# Sheet1.net
KiCad netlist of a schematic drawn in Altium Designer
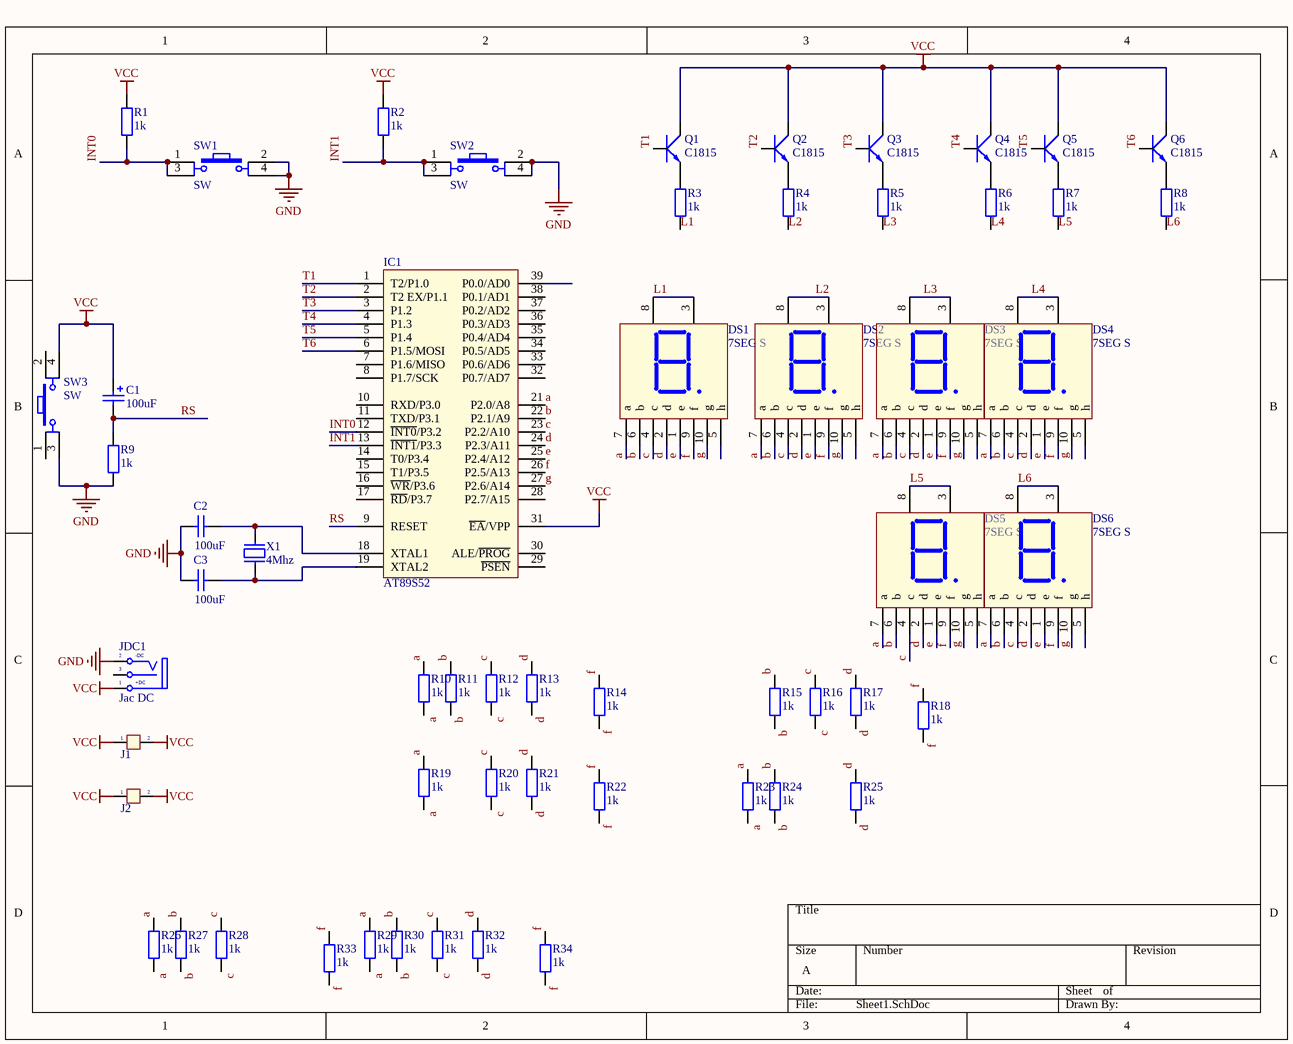
[diagram p0: Sheet1.SchDoc]

(export (version "E")
  (design (tool "Eeschema 10.0.6"))
  (components
    (comp (ref "C1")
      (value "100uF")
      (footprint "RADIAL C")
      (description "Polarized Capacitor")
      (fields (field (name "Comment") "Cap Pol") (field (name "PUBLISHER") "Altium Limited"))
      (libsource (lib "hphonglib") (part "Cap Pol"))
    )
    (comp (ref "C2")
      (value "100uF")
      (footprint "Cap Non-Pol 3mm")
      (description "Non-polarized Capacitor")
      (fields (field (name "Comment") "Cap Non-pol") (field (name "PUBLISHER") "Altium Limited"))
      (libsource (lib "hphonglib") (part "Cap Non-pol"))
    )
    (comp (ref "C3")
      (value "100uF")
      (footprint "Cap Non-Pol 3mm")
      (description "Non-polarized Capacitor")
      (fields (field (name "Comment") "Cap Non-pol") (field (name "PUBLISHER") "Altium Limited"))
      (libsource (lib "hphonglib") (part "Cap Non-pol"))
    )
    (comp (ref "DS1")
      (value "7SEG S")
      (footprint "7SEGS")
      (description "Single 7 Seg Dipslay")
      (libsource (lib "syhaunguyen") (part "LED7S"))
    )
    (comp (ref "DS2")
      (value "7SEG S")
      (footprint "7SEGS")
      (description "Single 7 Seg Dipslay")
      (libsource (lib "syhaunguyen") (part "LED7S"))
    )
    (comp (ref "DS3")
      (value "7SEG S")
      (footprint "7SEGS")
      (description "Single 7 Seg Dipslay")
      (libsource (lib "syhaunguyen") (part "LED7S"))
    )
    (comp (ref "DS4")
      (value "7SEG S")
      (footprint "7SEGS")
      (description "Single 7 Seg Dipslay")
      (libsource (lib "syhaunguyen") (part "LED7S"))
    )
    (comp (ref "DS5")
      (value "7SEG S")
      (footprint "7SEGS")
      (description "Single 7 Seg Dipslay")
      (libsource (lib "syhaunguyen") (part "LED7S"))
    )
    (comp (ref "DS6")
      (value "7SEG S")
      (footprint "7SEGS")
      (description "Single 7 Seg Dipslay")
      (libsource (lib "syhaunguyen") (part "LED7S"))
    )
    (comp (ref "IC1")
      (value "AT89S52")
      (footprint "DIP40/W0.6")
      (description "AT89S52, 8k Byte Flash Memory , 40 Pin")
      (libsource (lib "syhaunguyen") (part "AT89S52"))
    )
    (comp (ref "J1") (value "Jumper 2") (footprint "JP2") (libsource (lib "syhaunguyen") (part "JP 2")))
    (comp (ref "J2") (value "Jumper 2") (footprint "JP2") (libsource (lib "syhaunguyen") (part "JP 2")))
    (comp (ref "JDC1")
      (value "Jac DC")
      (footprint "DC-IN")
      (description "Jac DC input")
      (libsource (lib "syhaunguyen") (part "DCIN"))
    )
    (comp (ref "Q1")
      (value "C1815")
      (footprint "QTO-92")
      (description "NPN 600mW, ECB")
      (libsource (lib "hphonglib") (part "C1815_1"))
    )
    (comp (ref "Q2")
      (value "C1815")
      (footprint "QTO-92")
      (description "NPN 600mW, ECB")
      (libsource (lib "hphonglib") (part "C1815_1"))
    )
    (comp (ref "Q3")
      (value "C1815")
      (footprint "QTO-92")
      (description "NPN 600mW, ECB")
      (libsource (lib "hphonglib") (part "C1815_1"))
    )
    (comp (ref "Q4")
      (value "C1815")
      (footprint "QTO-92")
      (description "NPN 600mW, ECB")
      (libsource (lib "hphonglib") (part "C1815_1"))
    )
    (comp (ref "Q5")
      (value "C1815")
      (footprint "QTO-92")
      (description "NPN 600mW, ECB")
      (libsource (lib "hphonglib") (part "C1815_1"))
    )
    (comp (ref "Q6")
      (value "C1815")
      (footprint "QTO-92")
      (description "NPN 600mW, ECB")
      (libsource (lib "hphonglib") (part "C1815_1"))
    )
    (comp (ref "R1")
      (value "1k")
      (footprint "R1/4W")
      (description "Resistor 1/4W")
      (libsource (lib "syhaunguyen") (part "R1/4W"))
    )
    (comp (ref "R2")
      (value "1k")
      (footprint "R1/4W")
      (description "Resistor 1/4W")
      (libsource (lib "syhaunguyen") (part "R1/4W"))
    )
    (comp (ref "R3")
      (value "1k")
      (footprint "R1/4W")
      (description "Resistor 1/4W")
      (libsource (lib "syhaunguyen") (part "R1/4W"))
    )
    (comp (ref "R4")
      (value "1k")
      (footprint "R1/4W")
      (description "Resistor 1/4W")
      (libsource (lib "syhaunguyen") (part "R1/4W"))
    )
    (comp (ref "R5")
      (value "1k")
      (footprint "R1/4W")
      (description "Resistor 1/4W")
      (libsource (lib "syhaunguyen") (part "R1/4W"))
    )
    (comp (ref "R6")
      (value "1k")
      (footprint "R1/4W")
      (description "Resistor 1/4W")
      (libsource (lib "syhaunguyen") (part "R1/4W"))
    )
    (comp (ref "R7")
      (value "1k")
      (footprint "R1/4W")
      (description "Resistor 1/4W")
      (libsource (lib "syhaunguyen") (part "R1/4W"))
    )
    (comp (ref "R8")
      (value "1k")
      (footprint "R1/4W")
      (description "Resistor 1/4W")
      (libsource (lib "syhaunguyen") (part "R1/4W"))
    )
    (comp (ref "R9")
      (value "1k")
      (footprint "R1/4W")
      (description "Resistor 1/4W")
      (libsource (lib "syhaunguyen") (part "R1/4W"))
    )
    (comp (ref "R10")
      (value "1k")
      (footprint "R1/4W")
      (description "Resistor 1/4W")
      (libsource (lib "syhaunguyen") (part "R1/4W"))
    )
    (comp (ref "R11")
      (value "1k")
      (footprint "R1/4W")
      (description "Resistor 1/4W")
      (libsource (lib "syhaunguyen") (part "R1/4W"))
    )
    (comp (ref "R12")
      (value "1k")
      (footprint "R1/4W")
      (description "Resistor 1/4W")
      (libsource (lib "syhaunguyen") (part "R1/4W"))
    )
    (comp (ref "R13")
      (value "1k")
      (footprint "R1/4W")
      (description "Resistor 1/4W")
      (libsource (lib "syhaunguyen") (part "R1/4W"))
    )
    (comp (ref "R14")
      (value "1k")
      (footprint "R1/4W")
      (description "Resistor 1/4W")
      (libsource (lib "syhaunguyen") (part "R1/4W"))
    )
    (comp (ref "R15")
      (value "1k")
      (footprint "R1/4W")
      (description "Resistor 1/4W")
      (libsource (lib "syhaunguyen") (part "R1/4W"))
    )
    (comp (ref "R16")
      (value "1k")
      (footprint "R1/4W")
      (description "Resistor 1/4W")
      (libsource (lib "syhaunguyen") (part "R1/4W"))
    )
    (comp (ref "R17")
      (value "1k")
      (footprint "R1/4W")
      (description "Resistor 1/4W")
      (libsource (lib "syhaunguyen") (part "R1/4W"))
    )
    (comp (ref "R18")
      (value "1k")
      (footprint "R1/4W")
      (description "Resistor 1/4W")
      (libsource (lib "syhaunguyen") (part "R1/4W"))
    )
    (comp (ref "R19")
      (value "1k")
      (footprint "R1/4W")
      (description "Resistor 1/4W")
      (libsource (lib "syhaunguyen") (part "R1/4W"))
    )
    (comp (ref "R20")
      (value "1k")
      (footprint "R1/4W")
      (description "Resistor 1/4W")
      (libsource (lib "syhaunguyen") (part "R1/4W"))
    )
    (comp (ref "R21")
      (value "1k")
      (footprint "R1/4W")
      (description "Resistor 1/4W")
      (libsource (lib "syhaunguyen") (part "R1/4W"))
    )
    (comp (ref "R22")
      (value "1k")
      (footprint "R1/4W")
      (description "Resistor 1/4W")
      (libsource (lib "syhaunguyen") (part "R1/4W"))
    )
    (comp (ref "R23")
      (value "1k")
      (footprint "R1/4W")
      (description "Resistor 1/4W")
      (libsource (lib "syhaunguyen") (part "R1/4W"))
    )
    (comp (ref "R24")
      (value "1k")
      (footprint "R1/4W")
      (description "Resistor 1/4W")
      (libsource (lib "syhaunguyen") (part "R1/4W"))
    )
    (comp (ref "R25")
      (value "1k")
      (footprint "R1/4W")
      (description "Resistor 1/4W")
      (libsource (lib "syhaunguyen") (part "R1/4W"))
    )
    (comp (ref "R26")
      (value "1k")
      (footprint "R1/4W")
      (description "Resistor 1/4W")
      (libsource (lib "syhaunguyen") (part "R1/4W"))
    )
    (comp (ref "R27")
      (value "1k")
      (footprint "R1/4W")
      (description "Resistor 1/4W")
      (libsource (lib "syhaunguyen") (part "R1/4W"))
    )
    (comp (ref "R28")
      (value "1k")
      (footprint "R1/4W")
      (description "Resistor 1/4W")
      (libsource (lib "syhaunguyen") (part "R1/4W"))
    )
    (comp (ref "R29")
      (value "1k")
      (footprint "R1/4W")
      (description "Resistor 1/4W")
      (libsource (lib "syhaunguyen") (part "R1/4W"))
    )
    (comp (ref "R30")
      (value "1k")
      (footprint "R1/4W")
      (description "Resistor 1/4W")
      (libsource (lib "syhaunguyen") (part "R1/4W"))
    )
    (comp (ref "R31")
      (value "1k")
      (footprint "R1/4W")
      (description "Resistor 1/4W")
      (libsource (lib "syhaunguyen") (part "R1/4W"))
    )
    (comp (ref "R32")
      (value "1k")
      (footprint "R1/4W")
      (description "Resistor 1/4W")
      (libsource (lib "syhaunguyen") (part "R1/4W"))
    )
    (comp (ref "R33")
      (value "1k")
      (footprint "R1/4W")
      (description "Resistor 1/4W")
      (libsource (lib "syhaunguyen") (part "R1/4W"))
    )
    (comp (ref "R34")
      (value "1k")
      (footprint "R1/4W")
      (description "Resistor 1/4W")
      (libsource (lib "syhaunguyen") (part "R1/4W"))
    )
    (comp (ref "SW1")
      (value "SW")
      (footprint "SW4")
      (description "Switch button 4 pin")
      (libsource (lib "syhaunguyen") (part "SW4"))
    )
    (comp (ref "SW2")
      (value "SW")
      (footprint "SW4")
      (description "Switch button 4 pin")
      (libsource (lib "syhaunguyen") (part "SW4"))
    )
    (comp (ref "SW3")
      (value "SW")
      (footprint "SW4")
      (description "Switch button 4 pin")
      (libsource (lib "") (part "SW4_1"))
    )
    (comp (ref "X1")
      (value "4Mhz")
      (footprint "XT2")
      (description "Crystal For all Crystal 2pin.")
      (libsource (lib "syhaunguyen") (part "XT2"))
    )
  )
  (nets
    (net (code "1") (name "/INT0") (class "Default")
      (node (ref "IC1") (pin "12") (pinfunction "~{INT0}/P3.2_12") (pintype "passive"))
      (node (ref "R1") (pin "2") (pinfunction "2_2") (pintype "passive"))
      (node (ref "SW1") (pin "1") (pintype "passive"))
      (node (ref "SW1") (pin "3") (pintype "passive"))
    )
    (net (code "2") (name "/INT1") (class "Default")
      (node (ref "IC1") (pin "13") (pinfunction "~{INT1}/P3.3_13") (pintype "passive"))
      (node (ref "R2") (pin "2") (pinfunction "2_2") (pintype "passive"))
      (node (ref "SW2") (pin "1") (pintype "passive"))
      (node (ref "SW2") (pin "3") (pintype "passive"))
    )
    (net (code "3") (name "/L1") (class "Default")
      (node (ref "DS1") (pin "3") (pinfunction "Vcc_3") (pintype "passive"))
      (node (ref "DS1") (pin "8") (pinfunction "Vcc_8") (pintype "passive"))
      (node (ref "R3") (pin "1") (pinfunction "1_1") (pintype "passive"))
    )
    (net (code "4") (name "/L2") (class "Default")
      (node (ref "DS2") (pin "3") (pinfunction "Vcc_3") (pintype "passive"))
      (node (ref "DS2") (pin "8") (pinfunction "Vcc_8") (pintype "passive"))
      (node (ref "R4") (pin "1") (pinfunction "1_1") (pintype "passive"))
    )
    (net (code "5") (name "/L3") (class "Default")
      (node (ref "DS3") (pin "3") (pinfunction "Vcc_3") (pintype "passive"))
      (node (ref "DS3") (pin "8") (pinfunction "Vcc_8") (pintype "passive"))
      (node (ref "R5") (pin "1") (pinfunction "1_1") (pintype "passive"))
    )
    (net (code "6") (name "/L4") (class "Default")
      (node (ref "DS4") (pin "3") (pinfunction "Vcc_3") (pintype "passive"))
      (node (ref "DS4") (pin "8") (pinfunction "Vcc_8") (pintype "passive"))
      (node (ref "R6") (pin "1") (pinfunction "1_1") (pintype "passive"))
    )
    (net (code "7") (name "/L5") (class "Default")
      (node (ref "DS5") (pin "3") (pinfunction "Vcc_3") (pintype "passive"))
      (node (ref "DS5") (pin "8") (pinfunction "Vcc_8") (pintype "passive"))
      (node (ref "R7") (pin "1") (pinfunction "1_1") (pintype "passive"))
    )
    (net (code "8") (name "/L6") (class "Default")
      (node (ref "DS6") (pin "3") (pinfunction "Vcc_3") (pintype "passive"))
      (node (ref "DS6") (pin "8") (pinfunction "Vcc_8") (pintype "passive"))
      (node (ref "R8") (pin "1") (pinfunction "1_1") (pintype "passive"))
    )
    (net (code "9") (name "/RS") (class "Default")
      (node (ref "C1") (pin "2") (pinfunction "2_2") (pintype "passive"))
      (node (ref "IC1") (pin "9") (pinfunction "RESET_9") (pintype "passive"))
      (node (ref "R9") (pin "2") (pinfunction "2_2") (pintype "passive"))
    )
    (net (code "10") (name "/T1") (class "Default")
      (node (ref "IC1") (pin "1") (pinfunction "T2/P1.0_1") (pintype "passive"))
      (node (ref "Q1") (pin "3") (pinfunction "B_3") (pintype "passive"))
    )
    (net (code "11") (name "/T2") (class "Default")
      (node (ref "IC1") (pin "2") (pinfunction "T2_EX/P1.1_2") (pintype "passive"))
      (node (ref "Q2") (pin "3") (pinfunction "B_3") (pintype "passive"))
    )
    (net (code "12") (name "/T3") (class "Default")
      (node (ref "IC1") (pin "3") (pinfunction "P1.2_3") (pintype "passive"))
      (node (ref "Q3") (pin "3") (pinfunction "B_3") (pintype "passive"))
    )
    (net (code "13") (name "/T4") (class "Default")
      (node (ref "IC1") (pin "4") (pinfunction "P1.3_4") (pintype "passive"))
      (node (ref "Q4") (pin "3") (pinfunction "B_3") (pintype "passive"))
    )
    (net (code "14") (name "/T5") (class "Default")
      (node (ref "IC1") (pin "5") (pinfunction "P1.4_5") (pintype "passive"))
      (node (ref "Q5") (pin "3") (pinfunction "B_3") (pintype "passive"))
    )
    (net (code "15") (name "/T6") (class "Default")
      (node (ref "IC1") (pin "6") (pinfunction "P1.5/MOSI_6") (pintype "passive"))
      (node (ref "Q6") (pin "3") (pinfunction "B_3") (pintype "passive"))
    )
    (net (code "16") (name "/a") (class "Default")
      (node (ref "DS1") (pin "7") (pinfunction "a_7") (pintype "passive"))
      (node (ref "DS2") (pin "7") (pinfunction "a_7") (pintype "passive"))
      (node (ref "DS3") (pin "7") (pinfunction "a_7") (pintype "passive"))
      (node (ref "DS4") (pin "7") (pinfunction "a_7") (pintype "passive"))
      (node (ref "DS5") (pin "7") (pinfunction "a_7") (pintype "passive"))
      (node (ref "DS6") (pin "7") (pinfunction "a_7") (pintype "passive"))
      (node (ref "IC1") (pin "21") (pinfunction "P2.0/A8_21") (pintype "passive"))
      (node (ref "R10") (pin "1") (pinfunction "1_1") (pintype "passive"))
      (node (ref "R10") (pin "2") (pinfunction "2_2") (pintype "passive"))
      (node (ref "R19") (pin "1") (pinfunction "1_1") (pintype "passive"))
      (node (ref "R19") (pin "2") (pinfunction "2_2") (pintype "passive"))
      (node (ref "R23") (pin "1") (pinfunction "1_1") (pintype "passive"))
      (node (ref "R23") (pin "2") (pinfunction "2_2") (pintype "passive"))
      (node (ref "R26") (pin "1") (pinfunction "1_1") (pintype "passive"))
      (node (ref "R26") (pin "2") (pinfunction "2_2") (pintype "passive"))
      (node (ref "R29") (pin "1") (pinfunction "1_1") (pintype "passive"))
      (node (ref "R29") (pin "2") (pinfunction "2_2") (pintype "passive"))
    )
    (net (code "17") (name "/b") (class "Default")
      (node (ref "DS1") (pin "6") (pinfunction "b_6") (pintype "passive"))
      (node (ref "DS2") (pin "6") (pinfunction "b_6") (pintype "passive"))
      (node (ref "DS3") (pin "6") (pinfunction "b_6") (pintype "passive"))
      (node (ref "DS4") (pin "6") (pinfunction "b_6") (pintype "passive"))
      (node (ref "DS5") (pin "6") (pinfunction "b_6") (pintype "passive"))
      (node (ref "DS6") (pin "6") (pinfunction "b_6") (pintype "passive"))
      (node (ref "IC1") (pin "22") (pinfunction "P2.1/A9_22") (pintype "passive"))
      (node (ref "R11") (pin "1") (pinfunction "1_1") (pintype "passive"))
      (node (ref "R11") (pin "2") (pinfunction "2_2") (pintype "passive"))
      (node (ref "R15") (pin "1") (pinfunction "1_1") (pintype "passive"))
      (node (ref "R15") (pin "2") (pinfunction "2_2") (pintype "passive"))
      (node (ref "R24") (pin "1") (pinfunction "1_1") (pintype "passive"))
      (node (ref "R24") (pin "2") (pinfunction "2_2") (pintype "passive"))
      (node (ref "R27") (pin "1") (pinfunction "1_1") (pintype "passive"))
      (node (ref "R27") (pin "2") (pinfunction "2_2") (pintype "passive"))
      (node (ref "R30") (pin "1") (pinfunction "1_1") (pintype "passive"))
      (node (ref "R30") (pin "2") (pinfunction "2_2") (pintype "passive"))
    )
    (net (code "18") (name "/c") (class "Default")
      (node (ref "DS1") (pin "4") (pinfunction "c_4") (pintype "passive"))
      (node (ref "DS2") (pin "4") (pinfunction "c_4") (pintype "passive"))
      (node (ref "DS3") (pin "4") (pinfunction "c_4") (pintype "passive"))
      (node (ref "DS4") (pin "4") (pinfunction "c_4") (pintype "passive"))
      (node (ref "DS5") (pin "4") (pinfunction "c_4") (pintype "passive"))
      (node (ref "DS6") (pin "4") (pinfunction "c_4") (pintype "passive"))
      (node (ref "IC1") (pin "23") (pinfunction "P2.2/A10_23") (pintype "passive"))
      (node (ref "R12") (pin "1") (pinfunction "1_1") (pintype "passive"))
      (node (ref "R12") (pin "2") (pinfunction "2_2") (pintype "passive"))
      (node (ref "R16") (pin "1") (pinfunction "1_1") (pintype "passive"))
      (node (ref "R16") (pin "2") (pinfunction "2_2") (pintype "passive"))
      (node (ref "R20") (pin "1") (pinfunction "1_1") (pintype "passive"))
      (node (ref "R20") (pin "2") (pinfunction "2_2") (pintype "passive"))
      (node (ref "R28") (pin "1") (pinfunction "1_1") (pintype "passive"))
      (node (ref "R28") (pin "2") (pinfunction "2_2") (pintype "passive"))
      (node (ref "R31") (pin "1") (pinfunction "1_1") (pintype "passive"))
      (node (ref "R31") (pin "2") (pinfunction "2_2") (pintype "passive"))
    )
    (net (code "19") (name "/d") (class "Default")
      (node (ref "DS1") (pin "2") (pinfunction "d_2") (pintype "passive"))
      (node (ref "DS2") (pin "2") (pinfunction "d_2") (pintype "passive"))
      (node (ref "DS3") (pin "2") (pinfunction "d_2") (pintype "passive"))
      (node (ref "DS4") (pin "2") (pinfunction "d_2") (pintype "passive"))
      (node (ref "DS5") (pin "2") (pinfunction "d_2") (pintype "passive"))
      (node (ref "DS6") (pin "2") (pinfunction "d_2") (pintype "passive"))
      (node (ref "IC1") (pin "24") (pinfunction "P2.3/A11_24") (pintype "passive"))
      (node (ref "R13") (pin "1") (pinfunction "1_1") (pintype "passive"))
      (node (ref "R13") (pin "2") (pinfunction "2_2") (pintype "passive"))
      (node (ref "R17") (pin "1") (pinfunction "1_1") (pintype "passive"))
      (node (ref "R17") (pin "2") (pinfunction "2_2") (pintype "passive"))
      (node (ref "R21") (pin "1") (pinfunction "1_1") (pintype "passive"))
      (node (ref "R21") (pin "2") (pinfunction "2_2") (pintype "passive"))
      (node (ref "R25") (pin "1") (pinfunction "1_1") (pintype "passive"))
      (node (ref "R25") (pin "2") (pinfunction "2_2") (pintype "passive"))
      (node (ref "R32") (pin "1") (pinfunction "1_1") (pintype "passive"))
      (node (ref "R32") (pin "2") (pinfunction "2_2") (pintype "passive"))
    )
    (net (code "20") (name "/e") (class "Default")
      (node (ref "DS1") (pin "1") (pinfunction "e_1") (pintype "passive"))
      (node (ref "DS2") (pin "1") (pinfunction "e_1") (pintype "passive"))
      (node (ref "DS3") (pin "1") (pinfunction "e_1") (pintype "passive"))
      (node (ref "DS4") (pin "1") (pinfunction "e_1") (pintype "passive"))
      (node (ref "DS5") (pin "1") (pinfunction "e_1") (pintype "passive"))
      (node (ref "DS6") (pin "1") (pinfunction "e_1") (pintype "passive"))
      (node (ref "IC1") (pin "25") (pinfunction "P2.4/A12_25") (pintype "passive"))
    )
    (net (code "21") (name "/f") (class "Default")
      (node (ref "DS1") (pin "9") (pinfunction "f_9") (pintype "passive"))
      (node (ref "DS2") (pin "9") (pinfunction "f_9") (pintype "passive"))
      (node (ref "DS3") (pin "9") (pinfunction "f_9") (pintype "passive"))
      (node (ref "DS4") (pin "9") (pinfunction "f_9") (pintype "passive"))
      (node (ref "DS5") (pin "9") (pinfunction "f_9") (pintype "passive"))
      (node (ref "DS6") (pin "9") (pinfunction "f_9") (pintype "passive"))
      (node (ref "IC1") (pin "26") (pinfunction "P2.5/A13_26") (pintype "passive"))
      (node (ref "R14") (pin "1") (pinfunction "1_1") (pintype "passive"))
      (node (ref "R14") (pin "2") (pinfunction "2_2") (pintype "passive"))
      (node (ref "R18") (pin "1") (pinfunction "1_1") (pintype "passive"))
      (node (ref "R18") (pin "2") (pinfunction "2_2") (pintype "passive"))
      (node (ref "R22") (pin "1") (pinfunction "1_1") (pintype "passive"))
      (node (ref "R22") (pin "2") (pinfunction "2_2") (pintype "passive"))
      (node (ref "R33") (pin "1") (pinfunction "1_1") (pintype "passive"))
      (node (ref "R33") (pin "2") (pinfunction "2_2") (pintype "passive"))
      (node (ref "R34") (pin "1") (pinfunction "1_1") (pintype "passive"))
      (node (ref "R34") (pin "2") (pinfunction "2_2") (pintype "passive"))
    )
    (net (code "22") (name "/g") (class "Default")
      (node (ref "DS1") (pin "10") (pinfunction "g_10") (pintype "passive"))
      (node (ref "DS2") (pin "10") (pinfunction "g_10") (pintype "passive"))
      (node (ref "DS3") (pin "10") (pinfunction "g_10") (pintype "passive"))
      (node (ref "DS4") (pin "10") (pinfunction "g_10") (pintype "passive"))
      (node (ref "DS5") (pin "10") (pinfunction "g_10") (pintype "passive"))
      (node (ref "DS6") (pin "10") (pinfunction "g_10") (pintype "passive"))
      (node (ref "IC1") (pin "27") (pinfunction "P2.6/A14_27") (pintype "passive"))
    )
    (net (code "23") (name "GND") (class "Default")
      (node (ref "C2") (pin "1") (pinfunction "1_1") (pintype "passive"))
      (node (ref "C3") (pin "1") (pinfunction "1_1") (pintype "passive"))
      (node (ref "IC1") (pin "20") (pinfunction "GND_20") (pintype "power_in"))
      (node (ref "JDC1") (pin "2") (pinfunction "TN_2") (pintype "passive"))
      (node (ref "R9") (pin "1") (pinfunction "1_1") (pintype "passive"))
      (node (ref "SW1") (pin "2") (pintype "passive"))
      (node (ref "SW1") (pin "4") (pintype "passive"))
      (node (ref "SW2") (pin "2") (pintype "passive"))
      (node (ref "SW2") (pin "4") (pintype "passive"))
      (node (ref "SW3") (pin "3") (pintype "passive"))
    )
    (net (code "24") (name "Net-(IC1-XTAL1)") (class "Default")
      (node (ref "C2") (pin "2") (pinfunction "2_2") (pintype "passive"))
      (node (ref "IC1") (pin "18") (pinfunction "XTAL1_18") (pintype "passive"))
      (node (ref "X1") (pin "1") (pinfunction "1_1") (pintype "passive"))
    )
    (net (code "25") (name "Net-(IC1-XTAL2)") (class "Default")
      (node (ref "C3") (pin "2") (pinfunction "2_2") (pintype "passive"))
      (node (ref "IC1") (pin "19") (pinfunction "XTAL2_19") (pintype "passive"))
      (node (ref "X1") (pin "2") (pinfunction "2_2") (pintype "passive"))
    )
    (net (code "26") (name "Net-(Q1-E)") (class "Default")
      (node (ref "Q1") (pin "1") (pinfunction "E_1") (pintype "passive"))
      (node (ref "R3") (pin "2") (pinfunction "2_2") (pintype "passive"))
    )
    (net (code "27") (name "Net-(Q2-E)") (class "Default")
      (node (ref "Q2") (pin "1") (pinfunction "E_1") (pintype "passive"))
      (node (ref "R4") (pin "2") (pinfunction "2_2") (pintype "passive"))
    )
    (net (code "28") (name "Net-(Q3-E)") (class "Default")
      (node (ref "Q3") (pin "1") (pinfunction "E_1") (pintype "passive"))
      (node (ref "R5") (pin "2") (pinfunction "2_2") (pintype "passive"))
    )
    (net (code "29") (name "Net-(Q4-E)") (class "Default")
      (node (ref "Q4") (pin "1") (pinfunction "E_1") (pintype "passive"))
      (node (ref "R6") (pin "2") (pinfunction "2_2") (pintype "passive"))
    )
    (net (code "30") (name "Net-(Q5-E)") (class "Default")
      (node (ref "Q5") (pin "1") (pinfunction "E_1") (pintype "passive"))
      (node (ref "R7") (pin "2") (pinfunction "2_2") (pintype "passive"))
    )
    (net (code "31") (name "Net-(Q6-E)") (class "Default")
      (node (ref "Q6") (pin "1") (pinfunction "E_1") (pintype "passive"))
      (node (ref "R8") (pin "2") (pinfunction "2_2") (pintype "passive"))
    )
    (net (code "32") (name "VCC") (class "Default")
      (node (ref "C1") (pin "1") (pinfunction "1_1") (pintype "passive"))
      (node (ref "IC1") (pin "31") (pinfunction "~{EA}/VPP_31") (pintype "passive"))
      (node (ref "IC1") (pin "40") (pinfunction "VCC_40") (pintype "power_in"))
      (node (ref "J1") (pin "1") (pinfunction "1_1") (pintype "passive"))
      (node (ref "J1") (pin "2") (pinfunction "2_2") (pintype "passive"))
      (node (ref "J2") (pin "1") (pinfunction "1_1") (pintype "passive"))
      (node (ref "J2") (pin "2") (pinfunction "2_2") (pintype "passive"))
      (node (ref "JDC1") (pin "1") (pinfunction "T_1") (pintype "passive"))
      (node (ref "Q1") (pin "2") (pinfunction "C_2") (pintype "passive"))
      (node (ref "Q2") (pin "2") (pinfunction "C_2") (pintype "passive"))
      (node (ref "Q3") (pin "2") (pinfunction "C_2") (pintype "passive"))
      (node (ref "Q4") (pin "2") (pinfunction "C_2") (pintype "passive"))
      (node (ref "Q5") (pin "2") (pinfunction "C_2") (pintype "passive"))
      (node (ref "Q6") (pin "2") (pinfunction "C_2") (pintype "passive"))
      (node (ref "R1") (pin "1") (pinfunction "1_1") (pintype "passive"))
      (node (ref "R2") (pin "1") (pinfunction "1_1") (pintype "passive"))
      (node (ref "SW3") (pin "4") (pintype "passive"))
    )
    (net (code "33") (name "unconnected-(DS1-h-Pad5)") (class "Default")
      (node (ref "DS1") (pin "5") (pinfunction "h_5") (pintype "passive"))
    )
    (net (code "34") (name "unconnected-(DS2-h-Pad5)") (class "Default")
      (node (ref "DS2") (pin "5") (pinfunction "h_5") (pintype "passive"))
    )
    (net (code "35") (name "unconnected-(DS3-h-Pad5)") (class "Default")
      (node (ref "DS3") (pin "5") (pinfunction "h_5") (pintype "passive"))
    )
    (net (code "36") (name "unconnected-(DS4-h-Pad5)") (class "Default")
      (node (ref "DS4") (pin "5") (pinfunction "h_5") (pintype "passive"))
    )
    (net (code "37") (name "unconnected-(DS5-h-Pad5)") (class "Default")
      (node (ref "DS5") (pin "5") (pinfunction "h_5") (pintype "passive"))
    )
    (net (code "38") (name "unconnected-(DS6-h-Pad5)") (class "Default")
      (node (ref "DS6") (pin "5") (pinfunction "h_5") (pintype "passive"))
    )
    (net (code "39") (name "unconnected-(IC1-ALE{slash}~{PROG}-Pad30)") (class "Default")
      (node (ref "IC1") (pin "30") (pinfunction "ALE/~{PROG}_30") (pintype "passive"))
    )
    (net (code "40") (name "unconnected-(IC1-P0.0{slash}AD0-Pad39)") (class "Default")
      (node (ref "IC1") (pin "39") (pinfunction "P0.0/AD0_39") (pintype "passive"))
    )
    (net (code "41") (name "unconnected-(IC1-P0.1{slash}AD1-Pad38)") (class "Default")
      (node (ref "IC1") (pin "38") (pinfunction "P0.1/AD1_38") (pintype "passive"))
    )
    (net (code "42") (name "unconnected-(IC1-P0.2{slash}AD2-Pad37)") (class "Default")
      (node (ref "IC1") (pin "37") (pinfunction "P0.2/AD2_37") (pintype "passive"))
    )
    (net (code "43") (name "unconnected-(IC1-P0.3{slash}AD3-Pad36)") (class "Default")
      (node (ref "IC1") (pin "36") (pinfunction "P0.3/AD3_36") (pintype "passive"))
    )
    (net (code "44") (name "unconnected-(IC1-P0.4{slash}AD4-Pad35)") (class "Default")
      (node (ref "IC1") (pin "35") (pinfunction "P0.4/AD4_35") (pintype "passive"))
    )
    (net (code "45") (name "unconnected-(IC1-P0.5{slash}AD5-Pad34)") (class "Default")
      (node (ref "IC1") (pin "34") (pinfunction "P0.5/AD5_34") (pintype "passive"))
    )
    (net (code "46") (name "unconnected-(IC1-P0.6{slash}AD6-Pad33)") (class "Default")
      (node (ref "IC1") (pin "33") (pinfunction "P0.6/AD6_33") (pintype "passive"))
    )
    (net (code "47") (name "unconnected-(IC1-P0.7{slash}AD7-Pad32)") (class "Default")
      (node (ref "IC1") (pin "32") (pinfunction "P0.7/AD7_32") (pintype "passive"))
    )
    (net (code "48") (name "unconnected-(IC1-P1.6{slash}MISO-Pad7)") (class "Default")
      (node (ref "IC1") (pin "7") (pinfunction "P1.6/MISO_7") (pintype "passive"))
    )
    (net (code "49") (name "unconnected-(IC1-P1.7{slash}SCK-Pad8)") (class "Default")
      (node (ref "IC1") (pin "8") (pinfunction "P1.7/SCK_8") (pintype "passive"))
    )
    (net (code "50") (name "unconnected-(IC1-P2.7{slash}A15-Pad28)") (class "Default")
      (node (ref "IC1") (pin "28") (pinfunction "P2.7/A15_28") (pintype "passive"))
    )
    (net (code "51") (name "unconnected-(IC1-RXD{slash}P3.0-Pad10)") (class "Default")
      (node (ref "IC1") (pin "10") (pinfunction "RXD/P3.0_10") (pintype "passive"))
    )
    (net (code "52") (name "unconnected-(IC1-T0{slash}P3.4-Pad14)") (class "Default")
      (node (ref "IC1") (pin "14") (pinfunction "T0/P3.4_14") (pintype "passive"))
    )
    (net (code "53") (name "unconnected-(IC1-T1{slash}P3.5-Pad15)") (class "Default")
      (node (ref "IC1") (pin "15") (pinfunction "T1/P3.5_15") (pintype "passive"))
    )
    (net (code "54") (name "unconnected-(IC1-TXD{slash}P3.1-Pad11)") (class "Default")
      (node (ref "IC1") (pin "11") (pinfunction "TXD/P3.1_11") (pintype "passive"))
    )
    (net (code "55") (name "unconnected-(IC1-~{PSEN}-Pad29)") (class "Default")
      (node (ref "IC1") (pin "29") (pinfunction "~{PSEN}_29") (pintype "passive"))
    )
    (net (code "56") (name "unconnected-(IC1-~{RD}{slash}P3.7-Pad17)") (class "Default")
      (node (ref "IC1") (pin "17") (pinfunction "~{RD}/P3.7_17") (pintype "passive"))
    )
    (net (code "57") (name "unconnected-(IC1-~{WR}{slash}P3.6-Pad16)") (class "Default")
      (node (ref "IC1") (pin "16") (pinfunction "~{WR}/P3.6_16") (pintype "passive"))
    )
    (net (code "58") (name "unconnected-(JDC1-S-Pad3)") (class "Default")
      (node (ref "JDC1") (pin "3") (pinfunction "S_3") (pintype "power_in"))
    )
    (net (code "59") (name "unconnected-(SW3-Pad1)") (class "Default")
      (node (ref "SW3") (pin "1") (pintype "passive"))
    )
    (net (code "60") (name "unconnected-(SW3-Pad2)") (class "Default")
      (node (ref "SW3") (pin "2") (pintype "passive"))
    )
  )
)
